# Laptimer.net
KiCad netlist of a schematic drawn in EAGLE
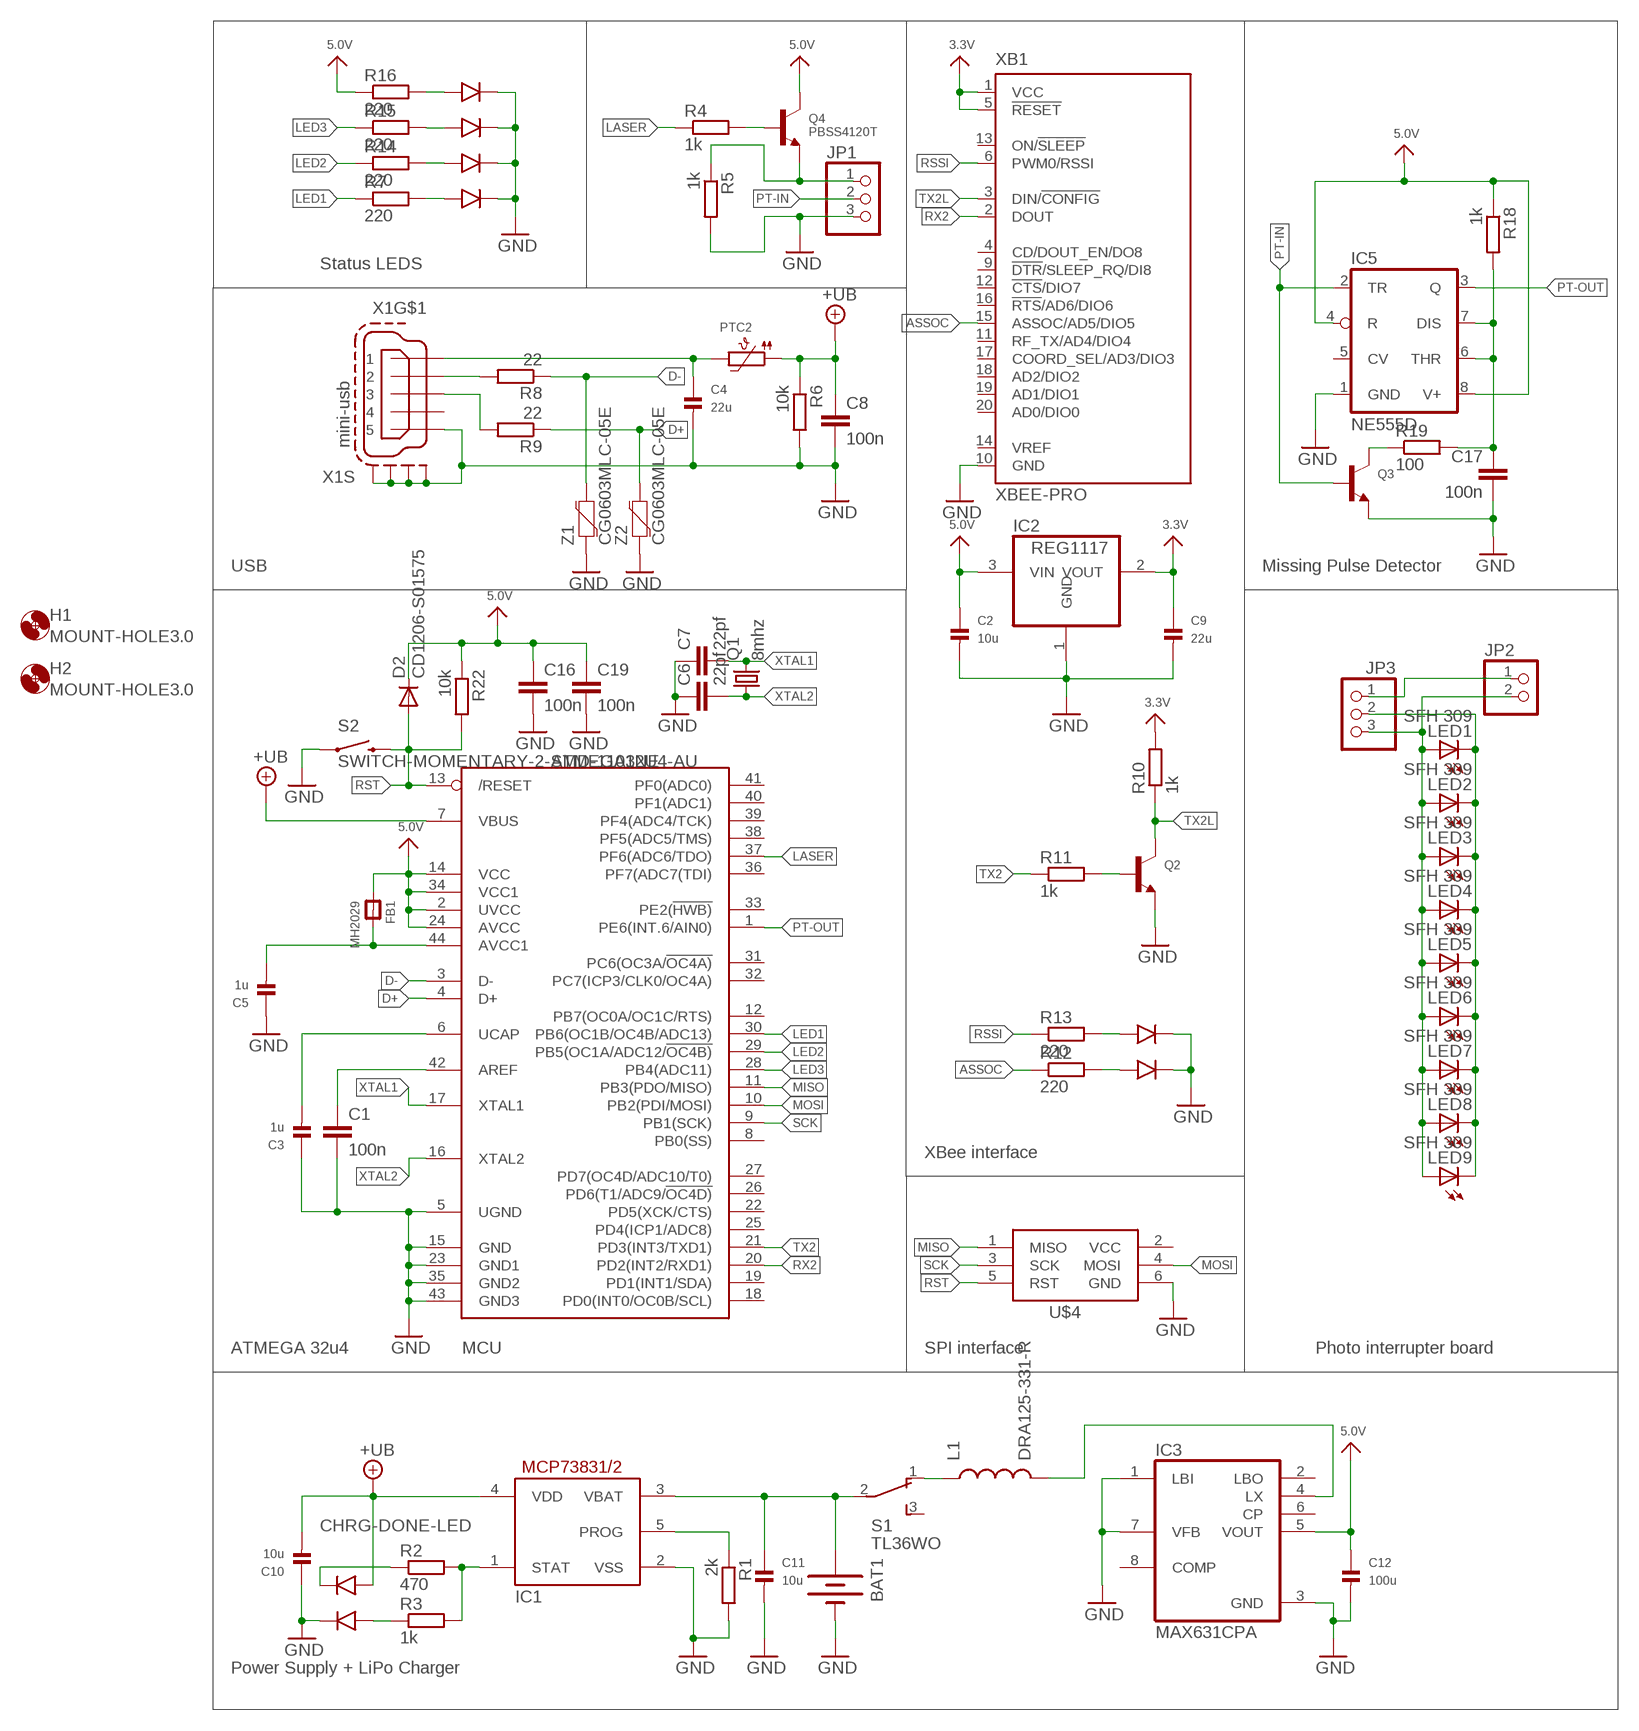
[diagram p0: schematic, sheet 1]

(export (version "E")
  (design (tool "Eeschema 10.0.6"))
  (components
    (comp (ref "BAT1")
      (value "BATTERY18650")
      (footprint "eagle-import:BATTERY_18650-HOLDER")
      (libsource (lib "eagle-import") (part "BATTERY18650"))
    )
    (comp (ref "C1")
      (value "100n")
      (footprint "eagle-import:C0603K")
      (libsource (lib "eagle-import") (part "C-EUC0603K"))
    )
    (comp (ref "C2")
      (value "10u")
      (footprint "eagle-import:_0805")
      (libsource (lib "eagle-import") (part "CAP_CERAMIC_0805"))
    )
    (comp (ref "C3")
      (value "1u")
      (footprint "eagle-import:_0805MP")
      (libsource (lib "eagle-import") (part "CAP_CERAMIC_0805MP"))
    )
    (comp (ref "C4")
      (value "22u")
      (footprint "eagle-import:_0805MP")
      (libsource (lib "eagle-import") (part "CAP_CERAMIC_0805MP"))
    )
    (comp (ref "C5")
      (value "1u")
      (footprint "eagle-import:_0805MP")
      (libsource (lib "eagle-import") (part "CAP_CERAMIC_0805MP"))
    )
    (comp (ref "C6")
      (value "22pf")
      (footprint "eagle-import:C0603K")
      (libsource (lib "eagle-import") (part "C-EUC0603K"))
    )
    (comp (ref "C7")
      (value "22pf")
      (footprint "eagle-import:C0603K")
      (libsource (lib "eagle-import") (part "C-EUC0603K"))
    )
    (comp (ref "C8")
      (value "100n")
      (footprint "eagle-import:C0603K")
      (libsource (lib "eagle-import") (part "C-EUC0603K"))
    )
    (comp (ref "C9")
      (value "22u")
      (footprint "eagle-import:_0805")
      (libsource (lib "eagle-import") (part "CAP_CERAMIC_0805"))
    )
    (comp (ref "C10")
      (value "10u")
      (footprint "eagle-import:_0805MP")
      (libsource (lib "eagle-import") (part "CAP_CERAMIC_0805MP"))
    )
    (comp (ref "C11")
      (value "10u")
      (footprint "eagle-import:_0805MP")
      (libsource (lib "eagle-import") (part "CAP_CERAMIC_0805MP"))
    )
    (comp (ref "C12")
      (value "100u")
      (footprint "eagle-import:1206")
      (libsource (lib "eagle-import") (part "CAP_CERAMIC1206"))
    )
    (comp (ref "C16")
      (value "100n")
      (footprint "eagle-import:C0603K")
      (libsource (lib "eagle-import") (part "C-EUC0603K"))
    )
    (comp (ref "C17")
      (value "100n")
      (footprint "eagle-import:C0603K")
      (libsource (lib "eagle-import") (part "C-EUC0603K"))
    )
    (comp (ref "C19")
      (value "100n")
      (footprint "eagle-import:C0603K")
      (libsource (lib "eagle-import") (part "C-EUC0603K"))
    )
    (comp (ref "D2")
      (value "CD1206-S01575")
      (footprint "eagle-import:MINIMELF")
      (libsource (lib "eagle-import") (part "DIODE-MINIMELF"))
    )
    (comp (ref "FB1")
      (value "MH2029")
      (footprint "eagle-import:_0805MP")
      (libsource (lib "eagle-import") (part "FERRITE_0805MP"))
    )
    (comp (ref "H1")
      (value "MOUNT-HOLE3.0")
      (footprint "eagle-import:3,0")
      (libsource (lib "eagle-import") (part "MOUNT-HOLE3.0"))
    )
    (comp (ref "H2")
      (value "MOUNT-HOLE3.0")
      (footprint "eagle-import:3,0")
      (libsource (lib "eagle-import") (part "MOUNT-HOLE3.0"))
    )
    (comp (ref "IC1")
      (value "MCP73831/OT")
      (footprint "eagle-import:SOT23-5L")
      (libsource (lib "eagle-import") (part "MCP73831/OT"))
    )
    (comp (ref "IC2")
      (value "REG1117")
      (footprint "eagle-import:SOT223")
      (libsource (lib "eagle-import") (part "REG1117"))
    )
    (comp (ref "IC3")
      (value "MAX631CPA")
      (footprint "eagle-import:DIL08")
      (libsource (lib "eagle-import") (part "MAX631CPA"))
    )
    (comp (ref "IC5")
      (value "NE555D")
      (footprint "eagle-import:SO08")
      (libsource (lib "eagle-import") (part "555DNE"))
    )
    (comp (ref "JP1")
      (value "PINHD-1X3")
      (footprint "eagle-import:1X03")
      (libsource (lib "eagle-import") (part "PINHD-1X3"))
    )
    (comp (ref "JP2")
      (value "HEADER-1X2ROUND")
      (footprint "eagle-import:1X02_ROUND")
      (libsource (lib "eagle-import") (part "HEADER-1X2ROUND"))
    )
    (comp (ref "JP3")
      (value "PINHD-1X3")
      (footprint "eagle-import:1X03")
      (libsource (lib "eagle-import") (part "PINHD-1X3"))
    )
    (comp (ref "L1")
      (value "DRA125-331-R")
      (footprint "eagle-import:CDRH125")
      (libsource (lib "eagle-import") (part "INDUCTORPWR"))
    )
    (comp (ref "LED1")
      (value "SFH 309")
      (footprint "eagle-import:LED3MM")
      (libsource (lib "eagle-import") (part "LED3MM"))
    )
    (comp (ref "LED2")
      (value "SFH 309")
      (footprint "eagle-import:LED3MM")
      (libsource (lib "eagle-import") (part "LED3MM"))
    )
    (comp (ref "LED3")
      (value "SFH 309")
      (footprint "eagle-import:LED3MM")
      (libsource (lib "eagle-import") (part "LED3MM"))
    )
    (comp (ref "LED4")
      (value "SFH 309")
      (footprint "eagle-import:LED3MM")
      (libsource (lib "eagle-import") (part "LED3MM"))
    )
    (comp (ref "LED5")
      (value "SFH 309")
      (footprint "eagle-import:LED3MM")
      (libsource (lib "eagle-import") (part "LED3MM"))
    )
    (comp (ref "LED6")
      (value "SFH 309")
      (footprint "eagle-import:LED3MM")
      (libsource (lib "eagle-import") (part "LED3MM"))
    )
    (comp (ref "LED7")
      (value "SFH 309")
      (footprint "eagle-import:LED3MM")
      (libsource (lib "eagle-import") (part "LED3MM"))
    )
    (comp (ref "LED8")
      (value "SFH 309")
      (footprint "eagle-import:LED3MM")
      (libsource (lib "eagle-import") (part "LED3MM"))
    )
    (comp (ref "LED9")
      (value "SFH 309")
      (footprint "eagle-import:LED3MM")
      (libsource (lib "eagle-import") (part "LED3MM"))
    )
    (comp (ref "MCU")
      (value "ATMEGA32U4-AU")
      (footprint "eagle-import:TQFP44")
      (libsource (lib "eagle-import") (part "ATMEGA32U4-AU"))
    )
    (comp (ref "PTC2")
      (value "PTC1206")
      (footprint "eagle-import:1206")
      (libsource (lib "eagle-import") (part "PTC1206"))
    )
    (comp (ref "Q1")
      (value "8mhz")
      (footprint "eagle-import:HC49_S")
      (libsource (lib "eagle-import") (part "CRYSTALHC49S"))
    )
    (comp (ref "Q2")
      (value "TRANSISTOR_NPNWIDE")
      (footprint "eagle-import:SOT23-WIDE")
      (libsource (lib "eagle-import") (part "TRANSISTOR_NPNWIDE"))
    )
    (comp (ref "Q3")
      (value "TRANSISTOR_NPNWIDE")
      (footprint "eagle-import:SOT23-WIDE")
      (libsource (lib "eagle-import") (part "TRANSISTOR_NPNWIDE"))
    )
    (comp (ref "Q4")
      (value "PBSS4120T")
      (footprint "eagle-import:SOT23-WIDE")
      (libsource (lib "eagle-import") (part "TRANSISTOR_NPNWIDE"))
    )
    (comp (ref "R1")
      (value "2k")
      (footprint "eagle-import:R0603")
      (libsource (lib "eagle-import") (part "R-EU_R0603"))
    )
    (comp (ref "R2")
      (value "470")
      (footprint "eagle-import:R0603")
      (libsource (lib "eagle-import") (part "R-EU_R0603"))
    )
    (comp (ref "R3")
      (value "1k")
      (footprint "eagle-import:R0603")
      (libsource (lib "eagle-import") (part "R-EU_R0603"))
    )
    (comp (ref "R4")
      (value "1k")
      (footprint "eagle-import:R0603")
      (libsource (lib "eagle-import") (part "R-EU_R0603"))
    )
    (comp (ref "R5")
      (value "1k")
      (footprint "eagle-import:R0603")
      (libsource (lib "eagle-import") (part "R-EU_R0603"))
    )
    (comp (ref "R6")
      (value "10k")
      (footprint "eagle-import:R0603")
      (libsource (lib "eagle-import") (part "R-EU_R0603"))
    )
    (comp (ref "R7")
      (value "220")
      (footprint "eagle-import:R0603")
      (libsource (lib "eagle-import") (part "R-EU_R0603"))
    )
    (comp (ref "R8")
      (value "22")
      (footprint "eagle-import:R0603")
      (libsource (lib "eagle-import") (part "R-EU_R0603"))
    )
    (comp (ref "R9")
      (value "22")
      (footprint "eagle-import:R0603")
      (libsource (lib "eagle-import") (part "R-EU_R0603"))
    )
    (comp (ref "R10")
      (value "1k")
      (footprint "eagle-import:R0603")
      (libsource (lib "eagle-import") (part "R-EU_R0603"))
    )
    (comp (ref "R11")
      (value "1k")
      (footprint "eagle-import:R0603")
      (libsource (lib "eagle-import") (part "R-EU_R0603"))
    )
    (comp (ref "R12")
      (value "220")
      (footprint "eagle-import:R0603")
      (libsource (lib "eagle-import") (part "R-EU_R0603"))
    )
    (comp (ref "R13")
      (value "220")
      (footprint "eagle-import:R0603")
      (libsource (lib "eagle-import") (part "R-EU_R0603"))
    )
    (comp (ref "R14")
      (value "220")
      (footprint "eagle-import:R0603")
      (libsource (lib "eagle-import") (part "R-EU_R0603"))
    )
    (comp (ref "R15")
      (value "220")
      (footprint "eagle-import:R0603")
      (libsource (lib "eagle-import") (part "R-EU_R0603"))
    )
    (comp (ref "R16")
      (value "220")
      (footprint "eagle-import:R0603")
      (libsource (lib "eagle-import") (part "R-EU_R0603"))
    )
    (comp (ref "R18")
      (value "1k")
      (footprint "eagle-import:R0603")
      (libsource (lib "eagle-import") (part "R-EU_R0603"))
    )
    (comp (ref "R19")
      (value "100")
      (footprint "eagle-import:R0603")
      (libsource (lib "eagle-import") (part "R-EU_R0603"))
    )
    (comp (ref "R22")
      (value "10k")
      (footprint "eagle-import:R0603")
      (libsource (lib "eagle-import") (part "R-EU_R0603"))
    )
    (comp (ref "S1")
      (value "TL36WO")
      (footprint "eagle-import:TL3XWO")
      (libsource (lib "eagle-import") (part "TL36WO"))
    )
    (comp (ref "S2")
      (value "SWITCH-MOMENTARY-2-SMD-1101NE")
      (footprint "eagle-import:TACTILE-SWITCH-1101NE")
      (libsource (lib "eagle-import") (part "SWITCH-MOMENTARY-2-SMD-1101NE"))
    )
    (comp (ref "U$1")
      (value "BI-LEVEL-LED-INDICATOR")
      (footprint "eagle-import:BI-LEVEL-LED-INDICATOR")
      (libsource (lib "eagle-import") (part "BI-LEVEL-LED-INDICATOR"))
    )
    (comp (ref "U$4")
      (value "AVRISP-BOX")
      (footprint "eagle-import:AVRISP-BOX")
      (libsource (lib "eagle-import") (part "AVRISP-BOX"))
    )
    (comp (ref "U$11")
      (value "BI-LEVEL-LED-INDICATOR")
      (footprint "eagle-import:BI-LEVEL-LED-INDICATOR")
      (libsource (lib "eagle-import") (part "BI-LEVEL-LED-INDICATOR"))
    )
    (comp (ref "U$18")
      (value "BI-LEVEL-LED-INDICATOR")
      (footprint "eagle-import:BI-LEVEL-LED-INDICATOR")
      (libsource (lib "eagle-import") (part "BI-LEVEL-LED-INDICATOR"))
    )
    (comp (ref "U$19")
      (value "BI-LEVEL-LED-INDICATOR")
      (footprint "eagle-import:BI-LEVEL-LED-INDICATOR")
      (libsource (lib "eagle-import") (part "BI-LEVEL-LED-INDICATOR"))
    )
    (comp (ref "X1")
      (value "mini-usb")
      (footprint "eagle-import:32005-301")
      (libsource (lib "eagle-import") (part "MINI-USB-SCHIELD-32005-301"))
    )
    (comp (ref "XB1")
      (value "XBEE-PRO")
      (footprint "eagle-import:XBEE-PRO")
      (libsource (lib "eagle-import") (part "XBEE-PRO"))
    )
    (comp (ref "Z1")
      (value "CG0603MLC-05E")
      (footprint "eagle-import:0603-RES")
      (libsource (lib "eagle-import") (part "VARISTOR-0603"))
    )
    (comp (ref "Z2")
      (value "CG0603MLC-05E")
      (footprint "eagle-import:0603-RES")
      (libsource (lib "eagle-import") (part "VARISTOR-0603"))
    )
  )
  (nets
    (net (code "1") (name "+UB") (class "Default")
      (node (ref "C10") (pin "2") (pinfunction "P$2_2") (pintype "passive"))
      (node (ref "C8") (pin "1") (pinfunction "1_1") (pintype "passive"))
      (node (ref "IC1") (pin "4") (pinfunction "VDD_4") (pintype "power_in"))
      (node (ref "MCU") (pin "7") (pinfunction "VBUS_7") (pintype "bidirectional"))
      (node (ref "PTC2") (pin "1") (pinfunction "1_1") (pintype "passive"))
      (node (ref "R6") (pin "1") (pinfunction "1_1") (pintype "passive"))
      (node (ref "U$1") (pin "ANODE1") (pinfunction "ANODE1_ANODE1") (pintype "bidirectional"))
    )
    (net (code "2") (name "/CHRG-DONE-LED") (class "Default")
      (node (ref "R3") (pin "1") (pinfunction "1_1") (pintype "passive"))
      (node (ref "U$1") (pin "ANODE2") (pinfunction "ANODE2_ANODE2") (pintype "bidirectional"))
    )
    (net (code "3") (name "/VCC") (class "Default")
      (node (ref "U$4") (pin "2") (pinfunction "VCC_2") (pintype "power_in"))
    )
    (net (code "4") (name "3.3V") (class "Default")
      (node (ref "C9") (pin "1") (pinfunction "P$1_1") (pintype "passive"))
      (node (ref "IC2") (pin "2") (pinfunction "VOUT_2") (pintype "output"))
      (node (ref "R10") (pin "2") (pinfunction "2_2") (pintype "passive"))
      (node (ref "XB1") (pin "1") (pinfunction "VCC_1") (pintype "power_in"))
      (node (ref "XB1") (pin "5") (pinfunction "~{RESET}_5") (pintype "input"))
    )
    (net (code "5") (name "5.0V") (class "Default")
      (node (ref "C12") (pin "1") (pinfunction "P$1_1") (pintype "passive"))
      (node (ref "C16") (pin "1") (pinfunction "1_1") (pintype "passive"))
      (node (ref "C19") (pin "1") (pinfunction "1_1") (pintype "passive"))
      (node (ref "C2") (pin "1") (pinfunction "P$1_1") (pintype "passive"))
      (node (ref "D2") (pin "C") (pinfunction "C_C") (pintype "passive"))
      (node (ref "FB1") (pin "1") (pinfunction "P$1_1") (pintype "passive"))
      (node (ref "IC2") (pin "3") (pinfunction "VIN_3") (pintype "input"))
      (node (ref "IC3") (pin "5") (pinfunction "VOUT_5") (pintype "output"))
      (node (ref "IC5") (pin "4") (pinfunction "R_4") (pintype "input"))
      (node (ref "IC5") (pin "8") (pinfunction "V+_8") (pintype "power_in"))
      (node (ref "MCU") (pin "14") (pinfunction "VCC_14") (pintype "bidirectional"))
      (node (ref "MCU") (pin "2") (pinfunction "UVCC_2") (pintype "bidirectional"))
      (node (ref "MCU") (pin "24") (pinfunction "AVCC_24") (pintype "bidirectional"))
      (node (ref "MCU") (pin "34") (pinfunction "VCC1_34") (pintype "bidirectional"))
      (node (ref "Q4") (pin "3") (pinfunction "C_3") (pintype "passive"))
      (node (ref "R16") (pin "1") (pinfunction "1_1") (pintype "passive"))
      (node (ref "R18") (pin "1") (pinfunction "1_1") (pintype "passive"))
      (node (ref "R22") (pin "1") (pinfunction "1_1") (pintype "passive"))
    )
    (net (code "6") (name "ASSOC") (class "Default")
      (node (ref "R12") (pin "1") (pinfunction "1_1") (pintype "passive"))
      (node (ref "XB1") (pin "15") (pinfunction "ASSOC/AD5/DIO5_15") (pintype "bidirectional"))
    )
    (net (code "7") (name "D+") (class "Default")
      (node (ref "MCU") (pin "4") (pinfunction "D+_4") (pintype "bidirectional"))
      (node (ref "R9") (pin "1") (pinfunction "1_1") (pintype "passive"))
      (node (ref "Z2") (pin "2") (pinfunction "2_2") (pintype "passive"))
    )
    (net (code "8") (name "D-") (class "Default")
      (node (ref "MCU") (pin "3") (pinfunction "D-_3") (pintype "bidirectional"))
      (node (ref "R8") (pin "1") (pinfunction "1_1") (pintype "passive"))
      (node (ref "Z1") (pin "2") (pinfunction "2_2") (pintype "passive"))
    )
    (net (code "9") (name "GND") (class "Default")
      (node (ref "BAT1") (pin "GND@1") (pinfunction "-_GND@1") (pintype "power_in"))
      (node (ref "C1") (pin "2") (pinfunction "2_2") (pintype "passive"))
      (node (ref "C10") (pin "1") (pinfunction "P$1_1") (pintype "passive"))
      (node (ref "C11") (pin "2") (pinfunction "P$2_2") (pintype "passive"))
      (node (ref "C12") (pin "2") (pinfunction "P$2_2") (pintype "passive"))
      (node (ref "C16") (pin "2") (pinfunction "2_2") (pintype "passive"))
      (node (ref "C17") (pin "2") (pinfunction "2_2") (pintype "passive"))
      (node (ref "C19") (pin "2") (pinfunction "2_2") (pintype "passive"))
      (node (ref "C2") (pin "2") (pinfunction "P$2_2") (pintype "passive"))
      (node (ref "C3") (pin "1") (pinfunction "P$1_1") (pintype "passive"))
      (node (ref "C4") (pin "2") (pinfunction "P$2_2") (pintype "passive"))
      (node (ref "C5") (pin "1") (pinfunction "P$1_1") (pintype "passive"))
      (node (ref "C6") (pin "1") (pinfunction "1_1") (pintype "passive"))
      (node (ref "C7") (pin "1") (pinfunction "1_1") (pintype "passive"))
      (node (ref "C8") (pin "2") (pinfunction "2_2") (pintype "passive"))
      (node (ref "C9") (pin "2") (pinfunction "P$2_2") (pintype "passive"))
      (node (ref "IC1") (pin "2") (pinfunction "VSS_2") (pintype "power_in"))
      (node (ref "IC2") (pin "1") (pinfunction "GND_1") (pintype "power_in"))
      (node (ref "IC3") (pin "1") (pinfunction "LBI_1") (pintype "input"))
      (node (ref "IC3") (pin "3") (pinfunction "GND_3") (pintype "power_in"))
      (node (ref "IC3") (pin "7") (pinfunction "VFB_7") (pintype "input"))
      (node (ref "IC5") (pin "1") (pinfunction "GND_1") (pintype "power_in"))
      (node (ref "JP1") (pin "3") (pinfunction "3_3") (pintype "passive"))
      (node (ref "MCU") (pin "15") (pinfunction "GND_15") (pintype "bidirectional"))
      (node (ref "MCU") (pin "23") (pinfunction "GND1_23") (pintype "bidirectional"))
      (node (ref "MCU") (pin "35") (pinfunction "GND2_35") (pintype "bidirectional"))
      (node (ref "MCU") (pin "43") (pinfunction "GND3_43") (pintype "bidirectional"))
      (node (ref "MCU") (pin "5") (pinfunction "UGND_5") (pintype "bidirectional"))
      (node (ref "Q2") (pin "2") (pinfunction "E_2") (pintype "passive"))
      (node (ref "Q3") (pin "2") (pinfunction "E_2") (pintype "passive"))
      (node (ref "R1") (pin "2") (pinfunction "2_2") (pintype "passive"))
      (node (ref "R5") (pin "2") (pinfunction "2_2") (pintype "passive"))
      (node (ref "R6") (pin "2") (pinfunction "2_2") (pintype "passive"))
      (node (ref "S2") (pin "P$1") (pinfunction "1_P$1") (pintype "passive"))
      (node (ref "U$1") (pin "CATHODE2") (pinfunction "CATHODE2_CATHODE2") (pintype "bidirectional"))
      (node (ref "U$11") (pin "CATHODE1") (pinfunction "CATHODE1_CATHODE1") (pintype "bidirectional"))
      (node (ref "U$11") (pin "CATHODE2") (pinfunction "CATHODE2_CATHODE2") (pintype "bidirectional"))
      (node (ref "U$18") (pin "CATHODE1") (pinfunction "CATHODE1_CATHODE1") (pintype "bidirectional"))
      (node (ref "U$18") (pin "CATHODE2") (pinfunction "CATHODE2_CATHODE2") (pintype "bidirectional"))
      (node (ref "U$19") (pin "CATHODE1") (pinfunction "CATHODE1_CATHODE1") (pintype "bidirectional"))
      (node (ref "U$19") (pin "CATHODE2") (pinfunction "CATHODE2_CATHODE2") (pintype "bidirectional"))
      (node (ref "U$4") (pin "6") (pinfunction "GND_6") (pintype "power_in"))
      (node (ref "X1") (pin "5") (pinfunction "5_5") (pintype "passive"))
      (node (ref "X1") (pin "M1") (pinfunction "S1_M1") (pintype "passive"))
      (node (ref "X1") (pin "M2") (pinfunction "S2_M2") (pintype "passive"))
      (node (ref "X1") (pin "M3") (pinfunction "S3_M3") (pintype "passive"))
      (node (ref "X1") (pin "M4") (pinfunction "S4_M4") (pintype "passive"))
      (node (ref "XB1") (pin "10") (pinfunction "GND_10") (pintype "power_in"))
      (node (ref "Z1") (pin "1") (pinfunction "1_1") (pintype "passive"))
      (node (ref "Z2") (pin "1") (pinfunction "1_1") (pintype "passive"))
    )
    (net (code "10") (name "LASER") (class "Default")
      (node (ref "MCU") (pin "37") (pinfunction "PF6(ADC6/TDO)_37") (pintype "bidirectional"))
      (node (ref "R4") (pin "1") (pinfunction "1_1") (pintype "passive"))
    )
    (net (code "11") (name "LED1") (class "Default")
      (node (ref "MCU") (pin "30") (pinfunction "PB6(OC1B/OC4B/ADC13)_30") (pintype "bidirectional"))
      (node (ref "R7") (pin "1") (pinfunction "1_1") (pintype "passive"))
    )
    (net (code "12") (name "LED2") (class "Default")
      (node (ref "MCU") (pin "29") (pinfunction "PB5(OC1A/ADC12/~{OC4B})_29") (pintype "bidirectional"))
      (node (ref "R14") (pin "1") (pinfunction "1_1") (pintype "passive"))
    )
    (net (code "13") (name "LED3") (class "Default")
      (node (ref "MCU") (pin "28") (pinfunction "PB4(ADC11)_28") (pintype "bidirectional"))
      (node (ref "R15") (pin "1") (pinfunction "1_1") (pintype "passive"))
    )
    (net (code "14") (name "MISO") (class "Default")
      (node (ref "MCU") (pin "11") (pinfunction "PB3(PDO/MISO)_11") (pintype "bidirectional"))
      (node (ref "U$4") (pin "1") (pinfunction "MISO_1") (pintype "input"))
    )
    (net (code "15") (name "MOSI") (class "Default")
      (node (ref "MCU") (pin "10") (pinfunction "PB2(PDI/MOSI)_10") (pintype "bidirectional"))
      (node (ref "U$4") (pin "4") (pinfunction "MOSI_4") (pintype "output"))
    )
    (net (code "16") (name "Net-(BAT1-+)") (class "Default")
      (node (ref "BAT1") (pin "PWR@1") (pinfunction "+_PWR@1") (pintype "power_in"))
      (node (ref "C11") (pin "1") (pinfunction "P$1_1") (pintype "passive"))
      (node (ref "IC1") (pin "3") (pinfunction "VBAT_3") (pintype "bidirectional"))
      (node (ref "S1") (pin "2") (pinfunction "P_2") (pintype "passive"))
    )
    (net (code "17") (name "Net-(C3-P$2)") (class "Default")
      (node (ref "C3") (pin "2") (pinfunction "P$2_2") (pintype "passive"))
      (node (ref "MCU") (pin "6") (pinfunction "UCAP_6") (pintype "bidirectional"))
    )
    (net (code "18") (name "Net-(C4-P$1)") (class "Default")
      (node (ref "C4") (pin "1") (pinfunction "P$1_1") (pintype "passive"))
      (node (ref "PTC2") (pin "2") (pinfunction "2_2") (pintype "passive"))
      (node (ref "X1") (pin "1") (pinfunction "1_1") (pintype "passive"))
    )
    (net (code "19") (name "Net-(C5-P$2)") (class "Default")
      (node (ref "C5") (pin "2") (pinfunction "P$2_2") (pintype "passive"))
      (node (ref "FB1") (pin "2") (pinfunction "P$2_2") (pintype "passive"))
      (node (ref "MCU") (pin "44") (pinfunction "AVCC1_44") (pintype "bidirectional"))
    )
    (net (code "20") (name "Net-(IC1-PROG)") (class "Default")
      (node (ref "IC1") (pin "5") (pinfunction "PROG_5") (pintype "input"))
      (node (ref "R1") (pin "1") (pinfunction "1_1") (pintype "passive"))
    )
    (net (code "21") (name "Net-(IC1-STAT)") (class "Default")
      (node (ref "IC1") (pin "1") (pinfunction "STAT_1") (pintype "output"))
      (node (ref "R2") (pin "2") (pinfunction "2_2") (pintype "passive"))
      (node (ref "R3") (pin "2") (pinfunction "2_2") (pintype "passive"))
    )
    (net (code "22") (name "Net-(IC3-LX)") (class "Default")
      (node (ref "IC3") (pin "4") (pinfunction "LX_4") (pintype "output"))
      (node (ref "L1") (pin "2") (pinfunction "2_2") (pintype "passive"))
    )
    (net (code "23") (name "Net-(IC5-DIS)") (class "Default")
      (node (ref "C17") (pin "1") (pinfunction "1_1") (pintype "passive"))
      (node (ref "IC5") (pin "6") (pinfunction "THR_6") (pintype "input"))
      (node (ref "IC5") (pin "7") (pinfunction "DIS_7") (pintype "input"))
      (node (ref "R18") (pin "2") (pinfunction "2_2") (pintype "passive"))
      (node (ref "R19") (pin "2") (pinfunction "2_2") (pintype "passive"))
    )
    (net (code "24") (name "Net-(JP2-Pad1)") (class "Default")
      (node (ref "JP2") (pin "1") (pinfunction "1_1") (pintype "passive"))
      (node (ref "JP3") (pin "1") (pinfunction "1_1") (pintype "passive"))
    )
    (net (code "25") (name "Net-(JP2-Pad2)") (class "Default")
      (node (ref "JP2") (pin "2") (pinfunction "2_2") (pintype "passive"))
      (node (ref "JP3") (pin "3") (pinfunction "3_3") (pintype "passive"))
      (node (ref "LED1") (pin "A") (pinfunction "A_A") (pintype "passive"))
      (node (ref "LED2") (pin "A") (pinfunction "A_A") (pintype "passive"))
      (node (ref "LED3") (pin "A") (pinfunction "A_A") (pintype "passive"))
      (node (ref "LED4") (pin "A") (pinfunction "A_A") (pintype "passive"))
      (node (ref "LED5") (pin "A") (pinfunction "A_A") (pintype "passive"))
      (node (ref "LED6") (pin "A") (pinfunction "A_A") (pintype "passive"))
      (node (ref "LED7") (pin "A") (pinfunction "A_A") (pintype "passive"))
      (node (ref "LED8") (pin "A") (pinfunction "A_A") (pintype "passive"))
      (node (ref "LED9") (pin "A") (pinfunction "A_A") (pintype "passive"))
    )
    (net (code "26") (name "Net-(LED1-C)") (class "Default")
      (node (ref "JP3") (pin "2") (pinfunction "2_2") (pintype "passive"))
      (node (ref "LED1") (pin "K") (pinfunction "C_K") (pintype "passive"))
      (node (ref "LED2") (pin "K") (pinfunction "C_K") (pintype "passive"))
      (node (ref "LED3") (pin "K") (pinfunction "C_K") (pintype "passive"))
      (node (ref "LED4") (pin "K") (pinfunction "C_K") (pintype "passive"))
      (node (ref "LED5") (pin "K") (pinfunction "C_K") (pintype "passive"))
      (node (ref "LED6") (pin "K") (pinfunction "C_K") (pintype "passive"))
      (node (ref "LED7") (pin "K") (pinfunction "C_K") (pintype "passive"))
      (node (ref "LED8") (pin "K") (pinfunction "C_K") (pintype "passive"))
      (node (ref "LED9") (pin "K") (pinfunction "C_K") (pintype "passive"))
    )
    (net (code "27") (name "Net-(MCU-AREF)") (class "Default")
      (node (ref "C1") (pin "1") (pinfunction "1_1") (pintype "passive"))
      (node (ref "MCU") (pin "42") (pinfunction "AREF_42") (pintype "bidirectional"))
    )
    (net (code "28") (name "Net-(Q2-B)") (class "Default")
      (node (ref "Q2") (pin "1") (pinfunction "B_1") (pintype "passive"))
      (node (ref "R11") (pin "2") (pinfunction "2_2") (pintype "passive"))
    )
    (net (code "29") (name "Net-(Q3-C)") (class "Default")
      (node (ref "Q3") (pin "3") (pinfunction "C_3") (pintype "passive"))
      (node (ref "R19") (pin "1") (pinfunction "1_1") (pintype "passive"))
    )
    (net (code "30") (name "Net-(Q4-B)") (class "Default")
      (node (ref "Q4") (pin "1") (pinfunction "B_1") (pintype "passive"))
      (node (ref "R4") (pin "2") (pinfunction "2_2") (pintype "passive"))
    )
    (net (code "31") (name "Net-(Q4-E)") (class "Default")
      (node (ref "JP1") (pin "1") (pinfunction "1_1") (pintype "passive"))
      (node (ref "Q4") (pin "2") (pinfunction "E_2") (pintype "passive"))
      (node (ref "R5") (pin "1") (pinfunction "1_1") (pintype "passive"))
    )
    (net (code "32") (name "Net-(R2-Pad1)") (class "Default")
      (node (ref "R2") (pin "1") (pinfunction "1_1") (pintype "passive"))
      (node (ref "U$1") (pin "CATHODE1") (pinfunction "CATHODE1_CATHODE1") (pintype "bidirectional"))
    )
    (net (code "33") (name "Net-(R7-Pad2)") (class "Default")
      (node (ref "R7") (pin "2") (pinfunction "2_2") (pintype "passive"))
      (node (ref "U$18") (pin "ANODE1") (pinfunction "ANODE1_ANODE1") (pintype "bidirectional"))
    )
    (net (code "34") (name "Net-(R8-Pad2)") (class "Default")
      (node (ref "R8") (pin "2") (pinfunction "2_2") (pintype "passive"))
      (node (ref "X1") (pin "2") (pinfunction "2_2") (pintype "passive"))
    )
    (net (code "35") (name "Net-(R9-Pad2)") (class "Default")
      (node (ref "R9") (pin "2") (pinfunction "2_2") (pintype "passive"))
      (node (ref "X1") (pin "3") (pinfunction "3_3") (pintype "passive"))
    )
    (net (code "36") (name "Net-(R12-Pad2)") (class "Default")
      (node (ref "R12") (pin "2") (pinfunction "2_2") (pintype "passive"))
      (node (ref "U$11") (pin "ANODE1") (pinfunction "ANODE1_ANODE1") (pintype "bidirectional"))
    )
    (net (code "37") (name "Net-(R13-Pad2)") (class "Default")
      (node (ref "R13") (pin "2") (pinfunction "2_2") (pintype "passive"))
      (node (ref "U$11") (pin "ANODE2") (pinfunction "ANODE2_ANODE2") (pintype "bidirectional"))
    )
    (net (code "38") (name "Net-(R14-Pad2)") (class "Default")
      (node (ref "R14") (pin "2") (pinfunction "2_2") (pintype "passive"))
      (node (ref "U$18") (pin "ANODE2") (pinfunction "ANODE2_ANODE2") (pintype "bidirectional"))
    )
    (net (code "39") (name "Net-(R15-Pad2)") (class "Default")
      (node (ref "R15") (pin "2") (pinfunction "2_2") (pintype "passive"))
      (node (ref "U$19") (pin "ANODE1") (pinfunction "ANODE1_ANODE1") (pintype "bidirectional"))
    )
    (net (code "40") (name "Net-(R16-Pad2)") (class "Default")
      (node (ref "R16") (pin "2") (pinfunction "2_2") (pintype "passive"))
      (node (ref "U$19") (pin "ANODE2") (pinfunction "ANODE2_ANODE2") (pintype "bidirectional"))
    )
    (net (code "41") (name "Net-(S1-O)") (class "Default")
      (node (ref "L1") (pin "1") (pinfunction "1_1") (pintype "passive"))
      (node (ref "S1") (pin "1") (pinfunction "O_1") (pintype "passive"))
    )
    (net (code "42") (name "PT-IN") (class "Default")
      (node (ref "IC5") (pin "2") (pinfunction "TR_2") (pintype "input"))
      (node (ref "JP1") (pin "2") (pinfunction "2_2") (pintype "passive"))
      (node (ref "Q3") (pin "1") (pinfunction "B_1") (pintype "passive"))
    )
    (net (code "43") (name "PT-OUT") (class "Default")
      (node (ref "IC5") (pin "3") (pinfunction "Q_3") (pintype "output"))
      (node (ref "MCU") (pin "1") (pinfunction "PE6(INT.6/AIN0)_1") (pintype "bidirectional"))
    )
    (net (code "44") (name "RSSI") (class "Default")
      (node (ref "R13") (pin "1") (pinfunction "1_1") (pintype "passive"))
      (node (ref "XB1") (pin "6") (pinfunction "PWM0/RSSI_6") (pintype "output"))
    )
    (net (code "45") (name "RST") (class "Default")
      (node (ref "D2") (pin "A") (pinfunction "A_A") (pintype "passive"))
      (node (ref "MCU") (pin "13") (pinfunction "/RESET_13") (pintype "bidirectional"))
      (node (ref "R22") (pin "2") (pinfunction "2_2") (pintype "passive"))
      (node (ref "S2") (pin "P$2") (pinfunction "2_P$2") (pintype "passive"))
      (node (ref "U$4") (pin "5") (pinfunction "RST_5") (pintype "output"))
    )
    (net (code "46") (name "RX2") (class "Default")
      (node (ref "MCU") (pin "20") (pinfunction "PD2(INT2/RXD1)_20") (pintype "bidirectional"))
      (node (ref "XB1") (pin "2") (pinfunction "DOUT_2") (pintype "output"))
    )
    (net (code "47") (name "SCK") (class "Default")
      (node (ref "MCU") (pin "9") (pinfunction "PB1(SCK)_9") (pintype "bidirectional"))
      (node (ref "U$4") (pin "3") (pinfunction "SCK_3") (pintype "output"))
    )
    (net (code "48") (name "TX2") (class "Default")
      (node (ref "MCU") (pin "21") (pinfunction "PD3(INT3/TXD1)_21") (pintype "bidirectional"))
      (node (ref "R11") (pin "1") (pinfunction "1_1") (pintype "passive"))
    )
    (net (code "49") (name "TX2L") (class "Default")
      (node (ref "Q2") (pin "3") (pinfunction "C_3") (pintype "passive"))
      (node (ref "R10") (pin "1") (pinfunction "1_1") (pintype "passive"))
      (node (ref "XB1") (pin "3") (pinfunction "DIN/~{CONFIG}_3") (pintype "input"))
    )
    (net (code "50") (name "XTAL1") (class "Default")
      (node (ref "C7") (pin "2") (pinfunction "2_2") (pintype "passive"))
      (node (ref "MCU") (pin "17") (pinfunction "XTAL1_17") (pintype "bidirectional"))
      (node (ref "Q1") (pin "2") (pinfunction "2_2") (pintype "passive"))
    )
    (net (code "51") (name "XTAL2") (class "Default")
      (node (ref "C6") (pin "2") (pinfunction "2_2") (pintype "passive"))
      (node (ref "MCU") (pin "16") (pinfunction "XTAL2_16") (pintype "bidirectional"))
      (node (ref "Q1") (pin "1") (pinfunction "1_1") (pintype "passive"))
    )
    (net (code "52") (name "unconnected-(IC3-COMP-Pad8)") (class "Default")
      (node (ref "IC3") (pin "8") (pinfunction "COMP_8") (pintype "input"))
    )
    (net (code "53") (name "unconnected-(IC3-CP-Pad6)") (class "Default")
      (node (ref "IC3") (pin "6") (pinfunction "CP_6") (pintype "output"))
    )
    (net (code "54") (name "unconnected-(IC3-LBO-Pad2)") (class "Default")
      (node (ref "IC3") (pin "2") (pinfunction "LBO_2") (pintype "output"))
    )
    (net (code "55") (name "unconnected-(IC5-CV-Pad5)") (class "Default")
      (node (ref "IC5") (pin "5") (pinfunction "CV_5") (pintype "input"))
    )
    (net (code "56") (name "unconnected-(MCU-PB0(SS)-Pad8)") (class "Default")
      (node (ref "MCU") (pin "8") (pinfunction "PB0(SS)_8") (pintype "bidirectional"))
    )
    (net (code "57") (name "unconnected-(MCU-PB7(OC0A{slash}OC1C{slash}RTS)-Pad12)") (class "Default")
      (node (ref "MCU") (pin "12") (pinfunction "PB7(OC0A/OC1C/RTS)_12") (pintype "bidirectional"))
    )
    (net (code "58") (name "unconnected-(MCU-PC6(OC3A{slash}~{OC4A})-Pad31)") (class "Default")
      (node (ref "MCU") (pin "31") (pinfunction "PC6(OC3A/~{OC4A})_31") (pintype "bidirectional"))
    )
    (net (code "59") (name "unconnected-(MCU-PC7(ICP3{slash}CLK0{slash}OC4A)-Pad32)") (class "Default")
      (node (ref "MCU") (pin "32") (pinfunction "PC7(ICP3/CLK0/OC4A)_32") (pintype "bidirectional"))
    )
    (net (code "60") (name "unconnected-(MCU-PD0(INT0{slash}OC0B{slash}SCL)-Pad18)") (class "Default")
      (node (ref "MCU") (pin "18") (pinfunction "PD0(INT0/OC0B/SCL)_18") (pintype "bidirectional"))
    )
    (net (code "61") (name "unconnected-(MCU-PD1(INT1{slash}SDA)-Pad19)") (class "Default")
      (node (ref "MCU") (pin "19") (pinfunction "PD1(INT1/SDA)_19") (pintype "bidirectional"))
    )
    (net (code "62") (name "unconnected-(MCU-PD4(ICP1{slash}ADC8)-Pad25)") (class "Default")
      (node (ref "MCU") (pin "25") (pinfunction "PD4(ICP1/ADC8)_25") (pintype "bidirectional"))
    )
    (net (code "63") (name "unconnected-(MCU-PD5(XCK{slash}CTS)-Pad22)") (class "Default")
      (node (ref "MCU") (pin "22") (pinfunction "PD5(XCK/CTS)_22") (pintype "bidirectional"))
    )
    (net (code "64") (name "unconnected-(MCU-PD6(T1{slash}ADC9{slash}~{OC4D})-Pad26)") (class "Default")
      (node (ref "MCU") (pin "26") (pinfunction "PD6(T1/ADC9/~{OC4D})_26") (pintype "bidirectional"))
    )
    (net (code "65") (name "unconnected-(MCU-PD7(OC4D{slash}ADC10{slash}T0)-Pad27)") (class "Default")
      (node (ref "MCU") (pin "27") (pinfunction "PD7(OC4D/ADC10/T0)_27") (pintype "bidirectional"))
    )
    (net (code "66") (name "unconnected-(MCU-PE2(~{HWB})-Pad33)") (class "Default")
      (node (ref "MCU") (pin "33") (pinfunction "PE2(~{HWB})_33") (pintype "bidirectional"))
    )
    (net (code "67") (name "unconnected-(MCU-PF0(ADC0)-Pad41)") (class "Default")
      (node (ref "MCU") (pin "41") (pinfunction "PF0(ADC0)_41") (pintype "bidirectional"))
    )
    (net (code "68") (name "unconnected-(MCU-PF1(ADC1)-Pad40)") (class "Default")
      (node (ref "MCU") (pin "40") (pinfunction "PF1(ADC1)_40") (pintype "bidirectional"))
    )
    (net (code "69") (name "unconnected-(MCU-PF4(ADC4{slash}TCK)-Pad39)") (class "Default")
      (node (ref "MCU") (pin "39") (pinfunction "PF4(ADC4/TCK)_39") (pintype "bidirectional"))
    )
    (net (code "70") (name "unconnected-(MCU-PF5(ADC5{slash}TMS)-Pad38)") (class "Default")
      (node (ref "MCU") (pin "38") (pinfunction "PF5(ADC5/TMS)_38") (pintype "bidirectional"))
    )
    (net (code "71") (name "unconnected-(MCU-PF7(ADC7(TDI)-Pad36)") (class "Default")
      (node (ref "MCU") (pin "36") (pinfunction "PF7(ADC7(TDI)_36") (pintype "bidirectional"))
    )
    (net (code "72") (name "unconnected-(S1-S-Pad3)") (class "Default")
      (node (ref "S1") (pin "3") (pinfunction "S_3") (pintype "passive"))
    )
    (net (code "73") (name "unconnected-(X1-Pad4)") (class "Default")
      (node (ref "X1") (pin "4") (pinfunction "4_4") (pintype "passive"))
    )
    (net (code "74") (name "unconnected-(XB1-AD0{slash}DIO0-Pad20)") (class "Default")
      (node (ref "XB1") (pin "20") (pinfunction "AD0/DIO0_20") (pintype "bidirectional"))
    )
    (net (code "75") (name "unconnected-(XB1-AD1{slash}DIO1-Pad19)") (class "Default")
      (node (ref "XB1") (pin "19") (pinfunction "AD1/DIO1_19") (pintype "bidirectional"))
    )
    (net (code "76") (name "unconnected-(XB1-AD2{slash}DIO2-Pad18)") (class "Default")
      (node (ref "XB1") (pin "18") (pinfunction "AD2/DIO2_18") (pintype "bidirectional"))
    )
    (net (code "77") (name "unconnected-(XB1-CD{slash}DOUT_EN{slash}DO8-Pad4)") (class "Default")
      (node (ref "XB1") (pin "4") (pinfunction "CD/DOUT_EN/DO8_4") (pintype "output"))
    )
    (net (code "78") (name "unconnected-(XB1-COORD_SEL{slash}AD3{slash}DIO3-Pad17)") (class "Default")
      (node (ref "XB1") (pin "17") (pinfunction "COORD_SEL/AD3/DIO3_17") (pintype "bidirectional"))
    )
    (net (code "79") (name "unconnected-(XB1-ON{slash}~{SLEEP}-Pad13)") (class "Default")
      (node (ref "XB1") (pin "13") (pinfunction "ON/~{SLEEP}_13") (pintype "output"))
    )
    (net (code "80") (name "unconnected-(XB1-RF_TX{slash}AD4{slash}DIO4-Pad11)") (class "Default")
      (node (ref "XB1") (pin "11") (pinfunction "RF_TX/AD4/DIO4_11") (pintype "bidirectional"))
    )
    (net (code "81") (name "unconnected-(XB1-VREF-Pad14)") (class "Default")
      (node (ref "XB1") (pin "14") (pinfunction "VREF_14") (pintype "input"))
    )
    (net (code "82") (name "unconnected-(XB1-~{CTS}{slash}DIO7-Pad12)") (class "Default")
      (node (ref "XB1") (pin "12") (pinfunction "~{CTS}/DIO7_12") (pintype "bidirectional"))
    )
    (net (code "83") (name "unconnected-(XB1-~{DTR}{slash}SLEEP_RQ{slash}DI8-Pad9)") (class "Default")
      (node (ref "XB1") (pin "9") (pinfunction "~{DTR}/SLEEP_RQ/DI8_9") (pintype "bidirectional"))
    )
    (net (code "84") (name "unconnected-(XB1-~{RTS}{slash}AD6{slash}DIO6-Pad16)") (class "Default")
      (node (ref "XB1") (pin "16") (pinfunction "~{RTS}/AD6/DIO6_16") (pintype "bidirectional"))
    )
  )
)
